# prominifinal-singlelayer.net
KiCad netlist of a schematic drawn in EAGLE
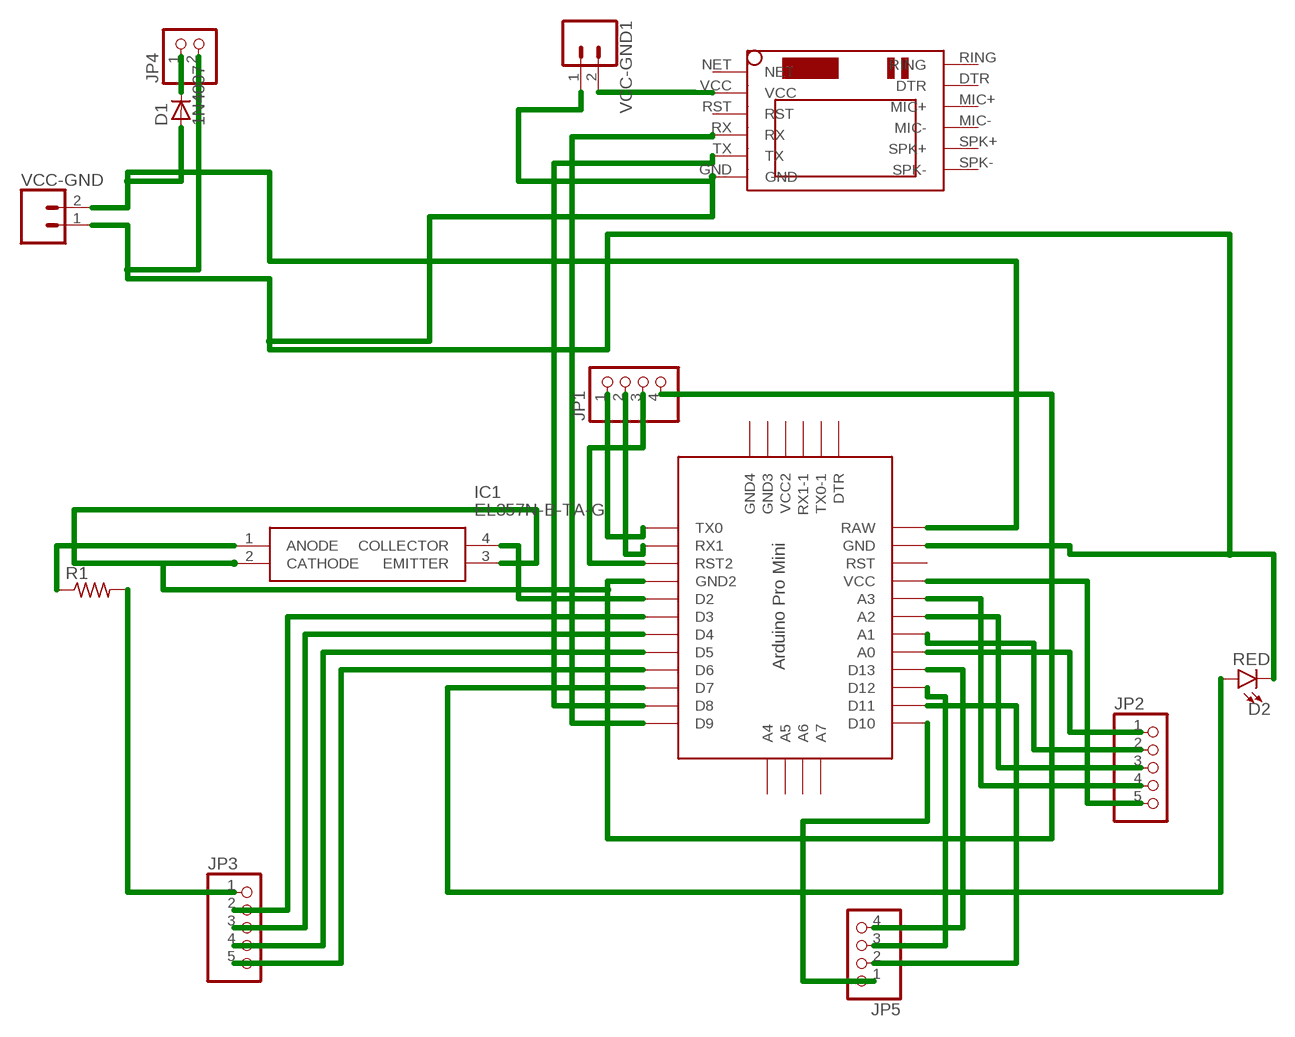
[diagram p0: schematic, sheet 1]

(export (version "E")
  (design (tool "Eeschema 10.0.6"))
  (components
    (comp (ref "D1")
      (value "1N4007")
      (footprint "eagle-import:SMA")
      (libsource (lib "eagle-import") (part "1N4007"))
    )
    (comp (ref "D2")
      (value "RED")
      (footprint "eagle-import:LED-1206")
      (libsource (lib "eagle-import") (part "LED-RED1206"))
    )
    (comp (ref "IC1")
      (value "EL357N-B-TA-G")
      (footprint "eagle-import:SOP254P700X200-4N")
      (libsource (lib "eagle-import") (part "EL357N-B-TA-G"))
    )
    (comp (ref "JP1")
      (value "PINHD-1X4")
      (footprint "eagle-import:1X04")
      (libsource (lib "eagle-import") (part "PINHD-1X4"))
    )
    (comp (ref "JP2")
      (value "PINHD-1X5")
      (footprint "eagle-import:1X05")
      (libsource (lib "eagle-import") (part "PINHD-1X5"))
    )
    (comp (ref "JP3")
      (value "PINHD-1X5")
      (footprint "eagle-import:1X05")
      (libsource (lib "eagle-import") (part "PINHD-1X5"))
    )
    (comp (ref "JP4")
      (value "PINHD-1X2")
      (footprint "eagle-import:1X02")
      (libsource (lib "eagle-import") (part "PINHD-1X2"))
    )
    (comp (ref "JP5")
      (value "PINHD-1X4")
      (footprint "eagle-import:1X04")
      (libsource (lib "eagle-import") (part "PINHD-1X4"))
    )
    (comp (ref "PROMINI")
      (value "PRO-MINI")
      (footprint "eagle-import:PRO-MINI")
      (libsource (lib "eagle-import") (part "PRO-MINI"))
    )
    (comp (ref "R1")
      (value "R-US_R1206")
      (footprint "eagle-import:R1206")
      (libsource (lib "eagle-import") (part "R-US_R1206"))
    )
    (comp (ref "U$1")
      (value "SIM800LMODULE")
      (footprint "eagle-import:SIM800LMODULE")
      (libsource (lib "eagle-import") (part "SIM800LMODULE"))
    )
    (comp (ref "VCC-GND")
      (value "CONN_025MM")
      (footprint "eagle-import:SCREWTERMINAL-5MM-2")
      (libsource (lib "eagle-import") (part "CONN_025MM"))
    )
    (comp (ref "VCC-GND1")
      (value "CONN_025MM")
      (footprint "eagle-import:SCREWTERMINAL-5MM-2")
      (libsource (lib "eagle-import") (part "CONN_025MM"))
    )
  )
  (nets
    (net (code "1") (name "Net-(D1-C)") (class "Default")
      (node (ref "D1") (pin "K") (pinfunction "C_K") (pintype "passive"))
      (node (ref "JP4") (pin "1") (pinfunction "1_1") (pintype "passive"))
    )
    (net (code "2") (name "Net-(D1-PadA)") (class "Default")
      (node (ref "D1") (pin "A") (pinfunction "A_A") (pintype "passive"))
      (node (ref "PROMINI") (pin "RAW") (pinfunction "RAW_RAW") (pintype "power_in"))
      (node (ref "VCC-GND") (pin "2") (pinfunction "2_2") (pintype "passive"))
    )
    (net (code "3") (name "Net-(D2-PadA)") (class "Default")
      (node (ref "D2") (pin "A") (pinfunction "A_A") (pintype "passive"))
      (node (ref "PROMINI") (pin "D7") (pinfunction "D7_D7") (pintype "bidirectional"))
    )
    (net (code "4") (name "Net-(D2-PadC)") (class "Default")
      (node (ref "D2") (pin "C") (pinfunction "C_C") (pintype "passive"))
      (node (ref "JP4") (pin "2") (pinfunction "2_2") (pintype "passive"))
      (node (ref "PROMINI") (pin "GND") (pinfunction "GND_GND") (pintype "input"))
      (node (ref "U$1") (pin "GND") (pinfunction "GND_GND") (pintype "bidirectional"))
      (node (ref "VCC-GND") (pin "1") (pinfunction "1_1") (pintype "passive"))
      (node (ref "VCC-GND1") (pin "1") (pinfunction "1_1") (pintype "passive"))
    )
    (net (code "5") (name "Net-(IC1-ANODE)") (class "Default")
      (node (ref "IC1") (pin "1") (pinfunction "ANODE_1") (pintype "bidirectional"))
      (node (ref "R1") (pin "1") (pinfunction "1_1") (pintype "passive"))
    )
    (net (code "6") (name "Net-(IC1-CATHODE)") (class "Default")
      (node (ref "IC1") (pin "2") (pinfunction "CATHODE_2") (pintype "bidirectional"))
      (node (ref "IC1") (pin "3") (pinfunction "EMITTER_3") (pintype "bidirectional"))
      (node (ref "JP1") (pin "4") (pinfunction "4_4") (pintype "passive"))
      (node (ref "PROMINI") (pin "GND1") (pinfunction "GND2_GND1") (pintype "bidirectional"))
    )
    (net (code "7") (name "Net-(IC1-COLLECTOR)") (class "Default")
      (node (ref "IC1") (pin "4") (pinfunction "COLLECTOR_4") (pintype "bidirectional"))
      (node (ref "PROMINI") (pin "D2") (pinfunction "D2_D2") (pintype "bidirectional"))
    )
    (net (code "8") (name "Net-(JP1-Pad1)") (class "Default")
      (node (ref "JP1") (pin "1") (pinfunction "1_1") (pintype "passive"))
      (node (ref "PROMINI") (pin "TX0") (pinfunction "TX0_TX0") (pintype "bidirectional"))
    )
    (net (code "9") (name "Net-(JP1-Pad2)") (class "Default")
      (node (ref "JP1") (pin "2") (pinfunction "2_2") (pintype "passive"))
      (node (ref "PROMINI") (pin "RX1") (pinfunction "RX1_RX1") (pintype "bidirectional"))
    )
    (net (code "10") (name "Net-(JP2-Pad1)") (class "Default")
      (node (ref "JP2") (pin "1") (pinfunction "1_1") (pintype "passive"))
      (node (ref "PROMINI") (pin "A0") (pinfunction "A0_A0") (pintype "bidirectional"))
    )
    (net (code "11") (name "Net-(JP2-Pad2)") (class "Default")
      (node (ref "JP2") (pin "2") (pinfunction "2_2") (pintype "passive"))
      (node (ref "PROMINI") (pin "A1") (pinfunction "A1_A1") (pintype "bidirectional"))
    )
    (net (code "12") (name "Net-(JP2-Pad3)") (class "Default")
      (node (ref "JP2") (pin "3") (pinfunction "3_3") (pintype "passive"))
      (node (ref "PROMINI") (pin "A2") (pinfunction "A2_A2") (pintype "bidirectional"))
    )
    (net (code "13") (name "Net-(JP2-Pad4)") (class "Default")
      (node (ref "JP2") (pin "4") (pinfunction "4_4") (pintype "passive"))
      (node (ref "PROMINI") (pin "A3") (pinfunction "A3_A3") (pintype "bidirectional"))
    )
    (net (code "14") (name "Net-(JP2-Pad5)") (class "Default")
      (node (ref "JP2") (pin "5") (pinfunction "5_5") (pintype "passive"))
      (node (ref "PROMINI") (pin "VCC") (pinfunction "VCC_VCC") (pintype "bidirectional"))
    )
    (net (code "15") (name "Net-(JP3-Pad1)") (class "Default")
      (node (ref "JP3") (pin "1") (pinfunction "1_1") (pintype "passive"))
      (node (ref "R1") (pin "2") (pinfunction "2_2") (pintype "passive"))
    )
    (net (code "16") (name "Net-(JP3-Pad2)") (class "Default")
      (node (ref "JP3") (pin "2") (pinfunction "2_2") (pintype "passive"))
      (node (ref "PROMINI") (pin "D3") (pinfunction "D3_D3") (pintype "bidirectional"))
    )
    (net (code "17") (name "Net-(JP3-Pad3)") (class "Default")
      (node (ref "JP3") (pin "3") (pinfunction "3_3") (pintype "passive"))
      (node (ref "PROMINI") (pin "D4") (pinfunction "D4_D4") (pintype "bidirectional"))
    )
    (net (code "18") (name "Net-(JP3-Pad4)") (class "Default")
      (node (ref "JP3") (pin "4") (pinfunction "4_4") (pintype "passive"))
      (node (ref "PROMINI") (pin "D5") (pinfunction "D5_D5") (pintype "bidirectional"))
    )
    (net (code "19") (name "Net-(JP3-Pad5)") (class "Default")
      (node (ref "JP3") (pin "5") (pinfunction "5_5") (pintype "passive"))
      (node (ref "PROMINI") (pin "D6") (pinfunction "D6_D6") (pintype "bidirectional"))
    )
    (net (code "20") (name "Net-(JP5-Pad1)") (class "Default")
      (node (ref "JP5") (pin "1") (pinfunction "1_1") (pintype "passive"))
      (node (ref "PROMINI") (pin "D10") (pinfunction "D10_D10") (pintype "bidirectional"))
    )
    (net (code "21") (name "Net-(JP5-Pad2)") (class "Default")
      (node (ref "JP5") (pin "2") (pinfunction "2_2") (pintype "passive"))
      (node (ref "PROMINI") (pin "D11") (pinfunction "D11_D11") (pintype "bidirectional"))
    )
    (net (code "22") (name "Net-(JP5-Pad3)") (class "Default")
      (node (ref "JP5") (pin "3") (pinfunction "3_3") (pintype "passive"))
      (node (ref "PROMINI") (pin "D12") (pinfunction "D12_D12") (pintype "bidirectional"))
    )
    (net (code "23") (name "Net-(JP5-Pad4)") (class "Default")
      (node (ref "JP5") (pin "4") (pinfunction "4_4") (pintype "passive"))
      (node (ref "PROMINI") (pin "D13") (pinfunction "D13_D13") (pintype "bidirectional"))
    )
    (net (code "24") (name "Net-(PROMINI-PadD8)") (class "Default")
      (node (ref "PROMINI") (pin "D8") (pinfunction "D8_D8") (pintype "bidirectional"))
      (node (ref "U$1") (pin "TX") (pinfunction "TX_TX") (pintype "bidirectional"))
    )
    (net (code "25") (name "Net-(PROMINI-PadD9)") (class "Default")
      (node (ref "PROMINI") (pin "D9") (pinfunction "D9_D9") (pintype "bidirectional"))
      (node (ref "U$1") (pin "RX") (pinfunction "RX_RX") (pintype "bidirectional"))
    )
    (net (code "26") (name "Net-(PROMINI-RST2)") (class "Default")
      (node (ref "JP1") (pin "3") (pinfunction "3_3") (pintype "passive"))
      (node (ref "PROMINI") (pin "RST1") (pinfunction "RST2_RST1") (pintype "bidirectional"))
    )
    (net (code "27") (name "Net-(U$1-PadVCC)") (class "Default")
      (node (ref "U$1") (pin "VCC") (pinfunction "VCC_VCC") (pintype "bidirectional"))
      (node (ref "VCC-GND1") (pin "2") (pinfunction "2_2") (pintype "passive"))
    )
    (net (code "28") (name "unconnected-(PROMINI-GND4-PadGND2)") (class "Default")
      (node (ref "PROMINI") (pin "GND2") (pinfunction "GND4_GND2") (pintype "bidirectional"))
    )
    (net (code "29") (name "unconnected-(PROMINI-PadA4)") (class "Default")
      (node (ref "PROMINI") (pin "A4") (pinfunction "A4_A4") (pintype "bidirectional"))
    )
    (net (code "30") (name "unconnected-(PROMINI-PadA5)") (class "Default")
      (node (ref "PROMINI") (pin "A5") (pinfunction "A5_A5") (pintype "bidirectional"))
    )
    (net (code "31") (name "unconnected-(PROMINI-PadA6)") (class "Default")
      (node (ref "PROMINI") (pin "A6") (pinfunction "A6_A6") (pintype "bidirectional"))
    )
    (net (code "32") (name "unconnected-(PROMINI-PadA7)") (class "Default")
      (node (ref "PROMINI") (pin "A7") (pinfunction "A7_A7") (pintype "bidirectional"))
    )
    (net (code "33") (name "unconnected-(PROMINI-PadDTR)") (class "Default")
      (node (ref "PROMINI") (pin "DTR") (pinfunction "DTR_DTR") (pintype "bidirectional"))
    )
    (net (code "34") (name "unconnected-(PROMINI-PadGND3)") (class "Default")
      (node (ref "PROMINI") (pin "GND3") (pinfunction "GND3_GND3") (pintype "bidirectional"))
    )
    (net (code "35") (name "unconnected-(PROMINI-PadRST)") (class "Default")
      (node (ref "PROMINI") (pin "RST") (pinfunction "RST_RST") (pintype "bidirectional"))
    )
    (net (code "36") (name "unconnected-(PROMINI-PadRX1-1)") (class "Default")
      (node (ref "PROMINI") (pin "RX1-1") (pinfunction "RX1-1_RX1-1") (pintype "bidirectional"))
    )
    (net (code "37") (name "unconnected-(PROMINI-PadTX0-1)") (class "Default")
      (node (ref "PROMINI") (pin "TX0-1") (pinfunction "TX0-1_TX0-1") (pintype "bidirectional"))
    )
    (net (code "38") (name "unconnected-(PROMINI-VCC2-PadVCC1)") (class "Default")
      (node (ref "PROMINI") (pin "VCC1") (pinfunction "VCC2_VCC1") (pintype "bidirectional"))
    )
    (net (code "39") (name "unconnected-(U$1-PadDTR)") (class "Default")
      (node (ref "U$1") (pin "DTR") (pinfunction "DTR_DTR") (pintype "bidirectional"))
    )
    (net (code "40") (name "unconnected-(U$1-PadMIC+)") (class "Default")
      (node (ref "U$1") (pin "MIC+") (pinfunction "MIC+_MIC+") (pintype "bidirectional"))
    )
    (net (code "41") (name "unconnected-(U$1-PadMIC-)") (class "Default")
      (node (ref "U$1") (pin "MIC-") (pinfunction "MIC-_MIC-") (pintype "bidirectional"))
    )
    (net (code "42") (name "unconnected-(U$1-PadNET)") (class "Default")
      (node (ref "U$1") (pin "NET") (pinfunction "NET_NET") (pintype "bidirectional"))
    )
    (net (code "43") (name "unconnected-(U$1-PadRING)") (class "Default")
      (node (ref "U$1") (pin "RING") (pinfunction "RING_RING") (pintype "bidirectional"))
    )
    (net (code "44") (name "unconnected-(U$1-PadRST)") (class "Default")
      (node (ref "U$1") (pin "RST") (pinfunction "RST_RST") (pintype "bidirectional"))
    )
    (net (code "45") (name "unconnected-(U$1-PadSPK+)") (class "Default")
      (node (ref "U$1") (pin "SPK+") (pinfunction "SPK+_SPK+") (pintype "bidirectional"))
    )
    (net (code "46") (name "unconnected-(U$1-PadSPK-)") (class "Default")
      (node (ref "U$1") (pin "SPK-") (pinfunction "SPK-_SPK-") (pintype "bidirectional"))
    )
  )
)
